# LED_Panel.net
KiCad netlist of a schematic drawn in Altium Designer
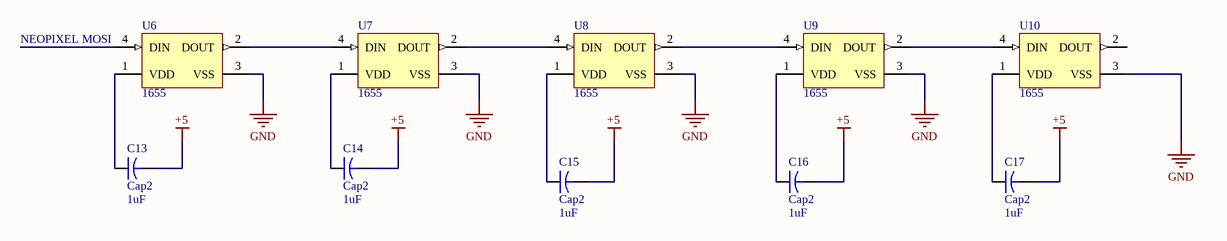
[diagram p0: LED_Panel.SchDoc]

(export (version "E")
  (design (tool "Eeschema 10.0.6"))
  (components
    (comp (ref "C13")
      (value "Cap2")
      (footprint "C0805")
      (description "Capacitor")
      (fields (field (name "ALTIUM_VALUE") "1uF") (field (name "PUBLISHER") "Altium Limited"))
      (libsource (lib "EE_Emerge_SkillsProject (1)") (part "Cap2_1"))
    )
    (comp (ref "C14")
      (value "Cap2")
      (footprint "C0805")
      (description "Capacitor")
      (fields (field (name "ALTIUM_VALUE") "1uF") (field (name "PUBLISHER") "Altium Limited"))
      (libsource (lib "EE_Emerge_SkillsProject (1)") (part "Cap2_1"))
    )
    (comp (ref "C15")
      (value "Cap2")
      (footprint "C0805")
      (description "Capacitor")
      (fields (field (name "ALTIUM_VALUE") "1uF") (field (name "PUBLISHER") "Altium Limited"))
      (libsource (lib "EE_Emerge_SkillsProject (1)") (part "Cap2_1"))
    )
    (comp (ref "C16")
      (value "Cap2")
      (footprint "C0805")
      (description "Capacitor")
      (fields (field (name "ALTIUM_VALUE") "1uF") (field (name "PUBLISHER") "Altium Limited"))
      (libsource (lib "EE_Emerge_SkillsProject (1)") (part "Cap2_1"))
    )
    (comp (ref "C17")
      (value "Cap2")
      (footprint "C0805")
      (description "Capacitor")
      (fields (field (name "ALTIUM_VALUE") "1uF") (field (name "PUBLISHER") "Altium Limited"))
      (libsource (lib "EE_Emerge_SkillsProject (1)") (part "Cap2_1"))
    )
    (comp (ref "U6")
      (value "1655")
      (footprint "ADA-RGB-1655_V")
      (fields (field (name "MANUFACTURER") "Adafruit-Industries-LLC"))
      (libsource (lib "Altium Content Vault") (part "ADA-RGB-1655-4"))
    )
    (comp (ref "U7")
      (value "1655")
      (footprint "ADA-RGB-1655_V")
      (fields (field (name "MANUFACTURER") "Adafruit-Industries-LLC"))
      (libsource (lib "Altium Content Vault") (part "ADA-RGB-1655-4"))
    )
    (comp (ref "U8")
      (value "1655")
      (footprint "ADA-RGB-1655_V")
      (fields (field (name "MANUFACTURER") "Adafruit-Industries-LLC"))
      (libsource (lib "Altium Content Vault") (part "ADA-RGB-1655-4"))
    )
    (comp (ref "U9")
      (value "1655")
      (footprint "ADA-RGB-1655_V")
      (fields (field (name "MANUFACTURER") "Adafruit-Industries-LLC"))
      (libsource (lib "Altium Content Vault") (part "ADA-RGB-1655-4"))
    )
    (comp (ref "U10")
      (value "1655")
      (footprint "ADA-RGB-1655_V")
      (fields (field (name "MANUFACTURER") "Adafruit-Industries-LLC"))
      (libsource (lib "Altium Content Vault") (part "ADA-RGB-1655-4"))
    )
  )
  (nets
    (net (code "1") (name "+5") (class "Default")
      (node (ref "C13") (pin "2") (pinfunction "2_2") (pintype "passive"))
      (node (ref "C14") (pin "2") (pinfunction "2_2") (pintype "passive"))
      (node (ref "C15") (pin "2") (pinfunction "2_2") (pintype "passive"))
      (node (ref "C16") (pin "2") (pinfunction "2_2") (pintype "passive"))
      (node (ref "C17") (pin "2") (pinfunction "2_2") (pintype "passive"))
    )
    (net (code "2") (name "GND") (class "Default")
      (node (ref "U10") (pin "3") (pinfunction "VSS_3") (pintype "power_in"))
      (node (ref "U6") (pin "3") (pinfunction "VSS_3") (pintype "power_in"))
      (node (ref "U7") (pin "3") (pinfunction "VSS_3") (pintype "power_in"))
      (node (ref "U8") (pin "3") (pinfunction "VSS_3") (pintype "power_in"))
      (node (ref "U9") (pin "3") (pinfunction "VSS_3") (pintype "power_in"))
    )
    (net (code "3") (name "Net-(U6-DOUT)") (class "Default")
      (node (ref "U6") (pin "2") (pinfunction "DOUT_2") (pintype "output"))
      (node (ref "U7") (pin "4") (pinfunction "DIN_4") (pintype "input"))
    )
    (net (code "4") (name "Net-(U6-VDD)") (class "Default")
      (node (ref "C13") (pin "1") (pinfunction "1_1") (pintype "passive"))
      (node (ref "U6") (pin "1") (pinfunction "VDD_1") (pintype "power_in"))
    )
    (net (code "5") (name "Net-(U7-DOUT)") (class "Default")
      (node (ref "U7") (pin "2") (pinfunction "DOUT_2") (pintype "output"))
      (node (ref "U8") (pin "4") (pinfunction "DIN_4") (pintype "input"))
    )
    (net (code "6") (name "Net-(U7-VDD)") (class "Default")
      (node (ref "C14") (pin "1") (pinfunction "1_1") (pintype "passive"))
      (node (ref "U7") (pin "1") (pinfunction "VDD_1") (pintype "power_in"))
    )
    (net (code "7") (name "Net-(U8-DOUT)") (class "Default")
      (node (ref "U8") (pin "2") (pinfunction "DOUT_2") (pintype "output"))
      (node (ref "U9") (pin "4") (pinfunction "DIN_4") (pintype "input"))
    )
    (net (code "8") (name "Net-(U8-VDD)") (class "Default")
      (node (ref "C15") (pin "1") (pinfunction "1_1") (pintype "passive"))
      (node (ref "U8") (pin "1") (pinfunction "VDD_1") (pintype "power_in"))
    )
    (net (code "9") (name "Net-(U9-VDD)") (class "Default")
      (node (ref "C16") (pin "1") (pinfunction "1_1") (pintype "passive"))
      (node (ref "U9") (pin "1") (pinfunction "VDD_1") (pintype "power_in"))
    )
    (net (code "10") (name "Net-(U10-DIN)") (class "Default")
      (node (ref "U10") (pin "4") (pinfunction "DIN_4") (pintype "input"))
      (node (ref "U9") (pin "2") (pinfunction "DOUT_2") (pintype "output"))
    )
    (net (code "11") (name "Net-(U10-VDD)") (class "Default")
      (node (ref "C17") (pin "1") (pinfunction "1_1") (pintype "passive"))
      (node (ref "U10") (pin "1") (pinfunction "VDD_1") (pintype "power_in"))
    )
    (net (code "12") (name "unconnected-(U6-DIN-Pad4)") (class "Default")
      (node (ref "U6") (pin "4") (pinfunction "DIN_4") (pintype "input"))
    )
    (net (code "13") (name "unconnected-(U10-DOUT-Pad2)") (class "Default")
      (node (ref "U10") (pin "2") (pinfunction "DOUT_2") (pintype "output"))
    )
  )
)
